# Chronos-Pad.net
KiCad netlist of a schematic drawn in EasyEDA Pro
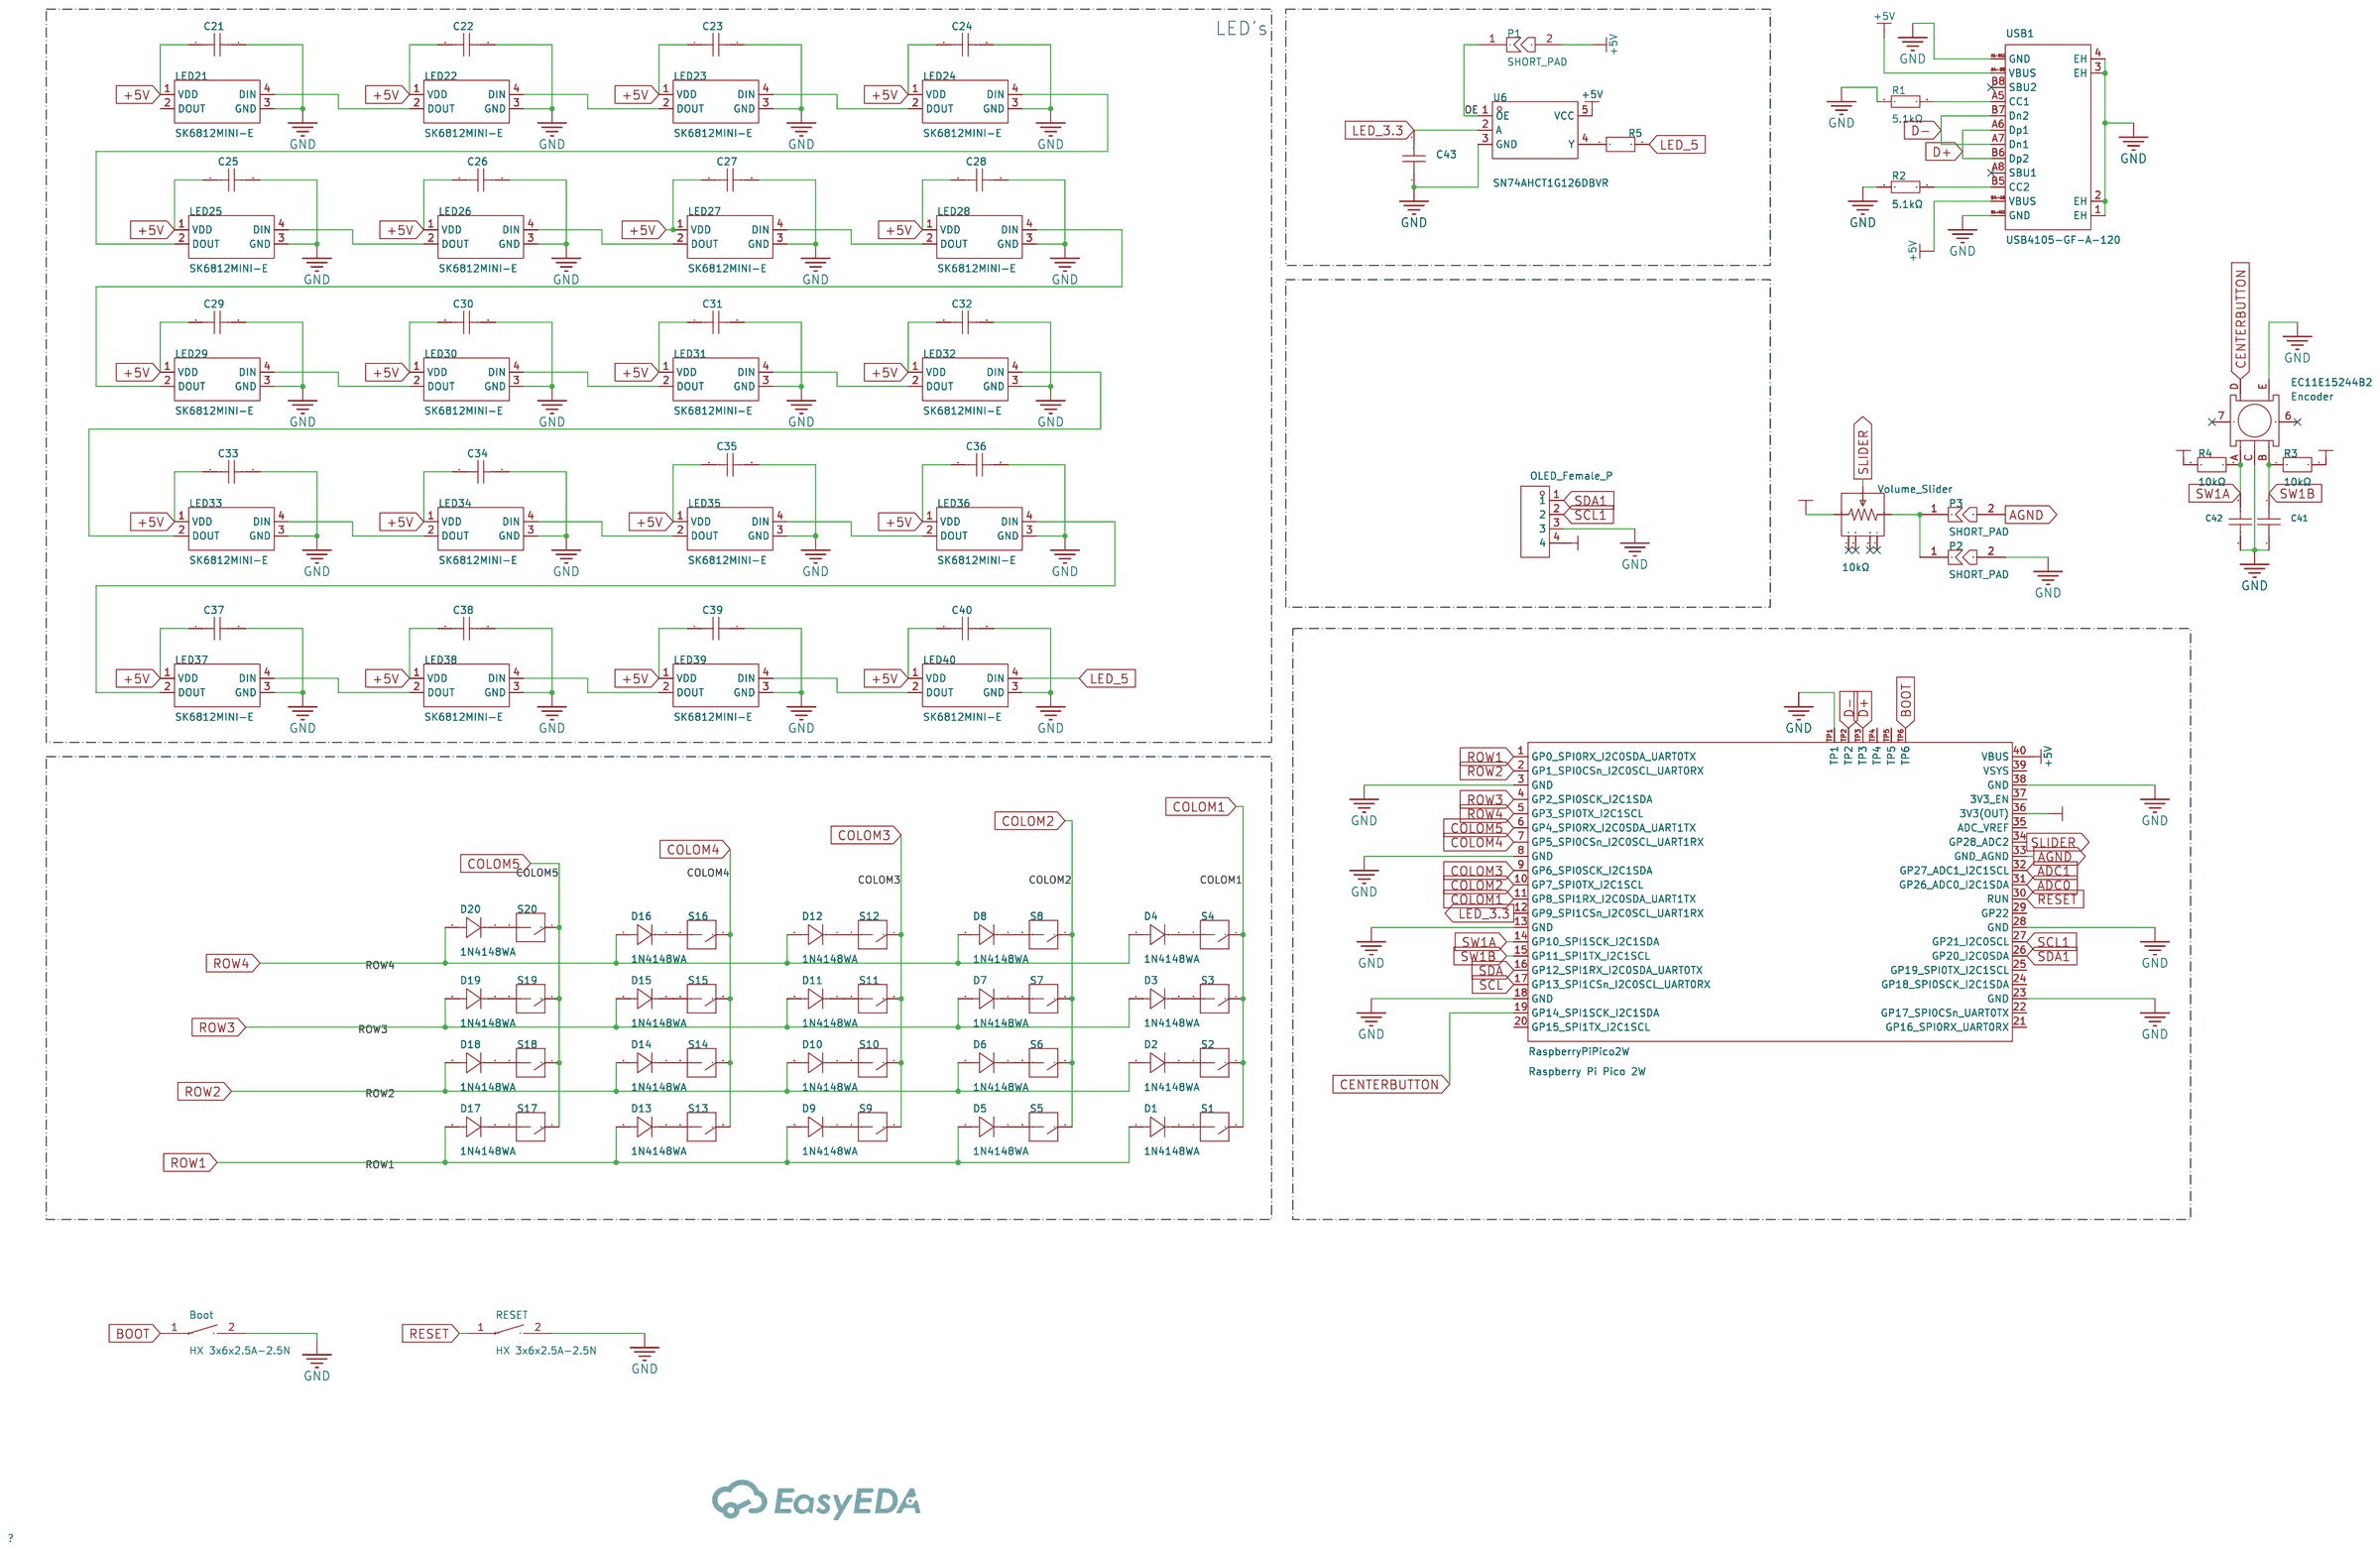
[diagram p0: schematic sheet]

(export (version "E")
  (design (tool "Eeschema 10.0.6"))
  (components
    (comp (ref "Boot")
      (value "HX 3x6x2.5A-2.5N")
      (footprint "easyedapro:SW-SMD_HX-TS-1101-C-W")
      (fields (field (name "Manufacturer") "hanxia(韩下)"))
      (libsource (lib "easyedapro") (part "HX TS-1101-C-W"))
    )
    (comp (ref "C21")
      (value "100nF")
      (footprint "easyedapro:C0603")
      (description "Capacitance:100nF Tolerance:±10% Tolerance:±10% Voltage Rating:50V Temperature Coefficient:X7R")
      (fields
        (field (name "Manufacturer Part") "CC0805KRX7R9BB104")
        (field (name "Manufacturer") "YAGEO(国巨)")
      )
      (libsource (lib "easyedapro") (part "NL0603B104M500CPBN"))
    )
    (comp (ref "C22")
      (value "100nF")
      (footprint "easyedapro:C0603")
      (description "Capacitance:100nF Tolerance:±10% Tolerance:±10% Voltage Rating:50V Temperature Coefficient:X7R")
      (fields
        (field (name "Manufacturer Part") "CC0805KRX7R9BB104")
        (field (name "Manufacturer") "YAGEO(国巨)")
      )
      (libsource (lib "easyedapro") (part "NL0603B104M500CPBN"))
    )
    (comp (ref "C23")
      (value "100nF")
      (footprint "easyedapro:C0603")
      (description "Capacitance:100nF Tolerance:±10% Tolerance:±10% Voltage Rating:50V Temperature Coefficient:X7R")
      (fields
        (field (name "Manufacturer Part") "CC0805KRX7R9BB104")
        (field (name "Manufacturer") "YAGEO(国巨)")
      )
      (libsource (lib "easyedapro") (part "NL0603B104M500CPBN"))
    )
    (comp (ref "C24")
      (value "100nF")
      (footprint "easyedapro:C0603")
      (description "Capacitance:100nF Tolerance:±10% Tolerance:±10% Voltage Rating:50V Temperature Coefficient:X7R")
      (fields
        (field (name "Manufacturer Part") "CC0805KRX7R9BB104")
        (field (name "Manufacturer") "YAGEO(国巨)")
      )
      (libsource (lib "easyedapro") (part "NL0603B104M500CPBN"))
    )
    (comp (ref "C25")
      (value "100nF")
      (footprint "easyedapro:C0603")
      (description "Capacitance:100nF Tolerance:±10% Tolerance:±10% Voltage Rating:50V Temperature Coefficient:X7R")
      (fields
        (field (name "Manufacturer Part") "CC0805KRX7R9BB104")
        (field (name "Manufacturer") "YAGEO(国巨)")
      )
      (libsource (lib "easyedapro") (part "NL0603B104M500CPBN"))
    )
    (comp (ref "C26")
      (value "100nF")
      (footprint "easyedapro:C0603")
      (description "Capacitance:100nF Tolerance:±10% Tolerance:±10% Voltage Rating:50V Temperature Coefficient:X7R")
      (fields
        (field (name "Manufacturer Part") "CC0805KRX7R9BB104")
        (field (name "Manufacturer") "YAGEO(国巨)")
      )
      (libsource (lib "easyedapro") (part "NL0603B104M500CPBN"))
    )
    (comp (ref "C27")
      (value "100nF")
      (footprint "easyedapro:C0603")
      (description "Capacitance:100nF Tolerance:±10% Tolerance:±10% Voltage Rating:50V Temperature Coefficient:X7R")
      (fields
        (field (name "Manufacturer Part") "CC0805KRX7R9BB104")
        (field (name "Manufacturer") "YAGEO(国巨)")
      )
      (libsource (lib "easyedapro") (part "NL0603B104M500CPBN"))
    )
    (comp (ref "C28")
      (value "100nF")
      (footprint "easyedapro:C0603")
      (description "Capacitance:100nF Tolerance:±10% Tolerance:±10% Voltage Rating:50V Temperature Coefficient:X7R")
      (fields
        (field (name "Manufacturer Part") "CC0805KRX7R9BB104")
        (field (name "Manufacturer") "YAGEO(国巨)")
      )
      (libsource (lib "easyedapro") (part "NL0603B104M500CPBN"))
    )
    (comp (ref "C29")
      (value "100nF")
      (footprint "easyedapro:C0603")
      (description "Capacitance:100nF Tolerance:±10% Tolerance:±10% Voltage Rating:50V Temperature Coefficient:X7R")
      (fields
        (field (name "Manufacturer Part") "CC0805KRX7R9BB104")
        (field (name "Manufacturer") "YAGEO(国巨)")
      )
      (libsource (lib "easyedapro") (part "NL0603B104M500CPBN"))
    )
    (comp (ref "C30")
      (value "100nF")
      (footprint "easyedapro:C0603")
      (description "Capacitance:100nF Tolerance:±10% Tolerance:±10% Voltage Rating:50V Temperature Coefficient:X7R")
      (fields
        (field (name "Manufacturer Part") "CC0805KRX7R9BB104")
        (field (name "Manufacturer") "YAGEO(国巨)")
      )
      (libsource (lib "easyedapro") (part "NL0603B104M500CPBN"))
    )
    (comp (ref "C31")
      (value "100nF")
      (footprint "easyedapro:C0603")
      (description "Capacitance:100nF Tolerance:±10% Tolerance:±10% Voltage Rating:50V Temperature Coefficient:X7R")
      (fields
        (field (name "Manufacturer Part") "CC0805KRX7R9BB104")
        (field (name "Manufacturer") "YAGEO(国巨)")
      )
      (libsource (lib "easyedapro") (part "NL0603B104M500CPBN"))
    )
    (comp (ref "C32")
      (value "100nF")
      (footprint "easyedapro:C0603")
      (description "Capacitance:100nF Tolerance:±10% Tolerance:±10% Voltage Rating:50V Temperature Coefficient:X7R")
      (fields
        (field (name "Manufacturer Part") "CC0805KRX7R9BB104")
        (field (name "Manufacturer") "YAGEO(国巨)")
      )
      (libsource (lib "easyedapro") (part "NL0603B104M500CPBN"))
    )
    (comp (ref "C33")
      (value "100nF")
      (footprint "easyedapro:C0603")
      (description "Capacitance:100nF Tolerance:±10% Tolerance:±10% Voltage Rating:50V Temperature Coefficient:X7R")
      (fields
        (field (name "Manufacturer Part") "CC0805KRX7R9BB104")
        (field (name "Manufacturer") "YAGEO(国巨)")
      )
      (libsource (lib "easyedapro") (part "NL0603B104M500CPBN"))
    )
    (comp (ref "C34")
      (value "100nF")
      (footprint "easyedapro:C0603")
      (description "Capacitance:100nF Tolerance:±10% Tolerance:±10% Voltage Rating:50V Temperature Coefficient:X7R")
      (fields
        (field (name "Manufacturer Part") "CC0805KRX7R9BB104")
        (field (name "Manufacturer") "YAGEO(国巨)")
      )
      (libsource (lib "easyedapro") (part "NL0603B104M500CPBN"))
    )
    (comp (ref "C35")
      (value "100nF")
      (footprint "easyedapro:C0603")
      (description "Capacitance:100nF Tolerance:±10% Tolerance:±10% Voltage Rating:50V Temperature Coefficient:X7R")
      (fields
        (field (name "Manufacturer Part") "CC0805KRX7R9BB104")
        (field (name "Manufacturer") "YAGEO(国巨)")
      )
      (libsource (lib "easyedapro") (part "NL0603B104M500CPBN"))
    )
    (comp (ref "C36")
      (value "100nF")
      (footprint "easyedapro:C0603")
      (description "Capacitance:100nF Tolerance:±10% Tolerance:±10% Voltage Rating:50V Temperature Coefficient:X7R")
      (fields
        (field (name "Manufacturer Part") "CC0805KRX7R9BB104")
        (field (name "Manufacturer") "YAGEO(国巨)")
      )
      (libsource (lib "easyedapro") (part "NL0603B104M500CPBN"))
    )
    (comp (ref "C37")
      (value "100nF")
      (footprint "easyedapro:C0603")
      (description "Capacitance:100nF Tolerance:±10% Tolerance:±10% Voltage Rating:50V Temperature Coefficient:X7R")
      (fields
        (field (name "Manufacturer Part") "CC0805KRX7R9BB104")
        (field (name "Manufacturer") "YAGEO(国巨)")
      )
      (libsource (lib "easyedapro") (part "NL0603B104M500CPBN"))
    )
    (comp (ref "C38")
      (value "100nF")
      (footprint "easyedapro:C0603")
      (description "Capacitance:100nF Tolerance:±10% Tolerance:±10% Voltage Rating:50V Temperature Coefficient:X7R")
      (fields
        (field (name "Manufacturer Part") "CC0805KRX7R9BB104")
        (field (name "Manufacturer") "YAGEO(国巨)")
      )
      (libsource (lib "easyedapro") (part "NL0603B104M500CPBN"))
    )
    (comp (ref "C39")
      (value "100nF")
      (footprint "easyedapro:C0603")
      (description "Capacitance:100nF Tolerance:±10% Tolerance:±10% Voltage Rating:50V Temperature Coefficient:X7R")
      (fields
        (field (name "Manufacturer Part") "CC0805KRX7R9BB104")
        (field (name "Manufacturer") "YAGEO(国巨)")
      )
      (libsource (lib "easyedapro") (part "NL0603B104M500CPBN"))
    )
    (comp (ref "C40")
      (value "100nF")
      (footprint "easyedapro:C0603")
      (description "Capacitance:100nF Tolerance:±10% Tolerance:±10% Voltage Rating:50V Temperature Coefficient:X7R")
      (fields
        (field (name "Manufacturer Part") "CC0805KRX7R9BB104")
        (field (name "Manufacturer") "YAGEO(国巨)")
      )
      (libsource (lib "easyedapro") (part "NL0603B104M500CPBN"))
    )
    (comp (ref "C41")
      (value "100nF")
      (footprint "easyedapro:C0805")
      (description "Capacitance:100nF Tolerance:±10% Tolerance:±10% Voltage Rating:50V Temperature Coefficient:X7R")
      (fields
        (field (name "Manufacturer Part") "CC0805KRX7R9BB104")
        (field (name "Manufacturer") "YAGEO(国巨)")
      )
      (libsource (lib "easyedapro") (part "CC0805JRX7R9BB103"))
    )
    (comp (ref "C42")
      (value "100nF")
      (footprint "easyedapro:C0805")
      (description "Capacitance:100nF Tolerance:±10% Tolerance:±10% Voltage Rating:50V Temperature Coefficient:X7R")
      (fields
        (field (name "Manufacturer Part") "CC0805KRX7R9BB104")
        (field (name "Manufacturer") "YAGEO(国巨)")
      )
      (libsource (lib "easyedapro") (part "CC0805JRX7R9BB103"))
    )
    (comp (ref "C43")
      (value "100nF")
      (footprint "easyedapro:C0603")
      (description "Capacitance:100nF Tolerance:±10% Tolerance:±10% Voltage Rating:50V Temperature Coefficient:X7R")
      (fields
        (field (name "Manufacturer Part") "CC0805KRX7R9BB104")
        (field (name "Manufacturer") "YAGEO(国巨)")
      )
      (libsource (lib "easyedapro") (part "NL0603B104M500CPBN"))
    )
    (comp (ref "D1")
      (value "1N4148WA")
      (footprint "easyedapro:SOD-323_L1.7-W1.3-LS2.7-RD")
      (fields (field (name "Manufacturer") "PJSEMI(平晶微)"))
      (libsource (lib "easyedapro") (part "1N4148WS_C5381436"))
    )
    (comp (ref "D2")
      (value "1N4148WA")
      (footprint "easyedapro:SOD-323_L1.7-W1.3-LS2.7-RD")
      (fields (field (name "Manufacturer") "PJSEMI(平晶微)"))
      (libsource (lib "easyedapro") (part "1N4148WS_C5381436"))
    )
    (comp (ref "D3")
      (value "1N4148WA")
      (footprint "easyedapro:SOD-323_L1.7-W1.3-LS2.7-RD")
      (fields (field (name "Manufacturer") "PJSEMI(平晶微)"))
      (libsource (lib "easyedapro") (part "1N4148WS_C5381436"))
    )
    (comp (ref "D4")
      (value "1N4148WA")
      (footprint "easyedapro:SOD-323_L1.7-W1.3-LS2.7-RD")
      (fields (field (name "Manufacturer") "PJSEMI(平晶微)"))
      (libsource (lib "easyedapro") (part "1N4148WS_C5381436"))
    )
    (comp (ref "D5")
      (value "1N4148WA")
      (footprint "easyedapro:SOD-323_L1.7-W1.3-LS2.7-RD")
      (fields (field (name "Manufacturer") "PJSEMI(平晶微)"))
      (libsource (lib "easyedapro") (part "1N4148WS_C5381436"))
    )
    (comp (ref "D6")
      (value "1N4148WA")
      (footprint "easyedapro:SOD-323_L1.7-W1.3-LS2.7-RD")
      (fields (field (name "Manufacturer") "PJSEMI(平晶微)"))
      (libsource (lib "easyedapro") (part "1N4148WS_C5381436"))
    )
    (comp (ref "D7")
      (value "1N4148WA")
      (footprint "easyedapro:SOD-323_L1.7-W1.3-LS2.7-RD")
      (fields (field (name "Manufacturer") "PJSEMI(平晶微)"))
      (libsource (lib "easyedapro") (part "1N4148WS_C5381436"))
    )
    (comp (ref "D8")
      (value "1N4148WA")
      (footprint "easyedapro:SOD-323_L1.7-W1.3-LS2.7-RD")
      (fields (field (name "Manufacturer") "PJSEMI(平晶微)"))
      (libsource (lib "easyedapro") (part "1N4148WS_C5381436"))
    )
    (comp (ref "D9")
      (value "1N4148WA")
      (footprint "easyedapro:SOD-323_L1.7-W1.3-LS2.7-RD")
      (fields (field (name "Manufacturer") "PJSEMI(平晶微)"))
      (libsource (lib "easyedapro") (part "1N4148WS_C5381436"))
    )
    (comp (ref "D10")
      (value "1N4148WA")
      (footprint "easyedapro:SOD-323_L1.7-W1.3-LS2.7-RD")
      (fields (field (name "Manufacturer") "PJSEMI(平晶微)"))
      (libsource (lib "easyedapro") (part "1N4148WS_C5381436"))
    )
    (comp (ref "D11")
      (value "1N4148WA")
      (footprint "easyedapro:SOD-323_L1.7-W1.3-LS2.7-RD")
      (fields (field (name "Manufacturer") "PJSEMI(平晶微)"))
      (libsource (lib "easyedapro") (part "1N4148WS_C5381436"))
    )
    (comp (ref "D12")
      (value "1N4148WA")
      (footprint "easyedapro:SOD-323_L1.7-W1.3-LS2.7-RD")
      (fields (field (name "Manufacturer") "PJSEMI(平晶微)"))
      (libsource (lib "easyedapro") (part "1N4148WS_C5381436"))
    )
    (comp (ref "D13")
      (value "1N4148WA")
      (footprint "easyedapro:SOD-323_L1.7-W1.3-LS2.7-RD")
      (fields (field (name "Manufacturer") "PJSEMI(平晶微)"))
      (libsource (lib "easyedapro") (part "1N4148WS_C5381436"))
    )
    (comp (ref "D14")
      (value "1N4148WA")
      (footprint "easyedapro:SOD-323_L1.7-W1.3-LS2.7-RD")
      (fields (field (name "Manufacturer") "PJSEMI(平晶微)"))
      (libsource (lib "easyedapro") (part "1N4148WS_C5381436"))
    )
    (comp (ref "D15")
      (value "1N4148WA")
      (footprint "easyedapro:SOD-323_L1.7-W1.3-LS2.7-RD")
      (fields (field (name "Manufacturer") "PJSEMI(平晶微)"))
      (libsource (lib "easyedapro") (part "1N4148WS_C5381436"))
    )
    (comp (ref "D16")
      (value "1N4148WA")
      (footprint "easyedapro:SOD-323_L1.7-W1.3-LS2.7-RD")
      (fields (field (name "Manufacturer") "PJSEMI(平晶微)"))
      (libsource (lib "easyedapro") (part "1N4148WS_C5381436"))
    )
    (comp (ref "D17")
      (value "1N4148WA")
      (footprint "easyedapro:SOD-323_L1.7-W1.3-LS2.7-RD")
      (fields (field (name "Manufacturer") "PJSEMI(平晶微)"))
      (libsource (lib "easyedapro") (part "1N4148WS_C5381436"))
    )
    (comp (ref "D18")
      (value "1N4148WA")
      (footprint "easyedapro:SOD-323_L1.7-W1.3-LS2.7-RD")
      (fields (field (name "Manufacturer") "PJSEMI(平晶微)"))
      (libsource (lib "easyedapro") (part "1N4148WS_C5381436"))
    )
    (comp (ref "D19")
      (value "1N4148WA")
      (footprint "easyedapro:SOD-323_L1.7-W1.3-LS2.7-RD")
      (fields (field (name "Manufacturer") "PJSEMI(平晶微)"))
      (libsource (lib "easyedapro") (part "1N4148WS_C5381436"))
    )
    (comp (ref "D20")
      (value "1N4148WA")
      (footprint "easyedapro:SOD-323_L1.7-W1.3-LS2.7-RD")
      (fields (field (name "Manufacturer") "PJSEMI(平晶微)"))
      (libsource (lib "easyedapro") (part "1N4148WS_C5381436"))
    )
    (comp (ref "Encoder")
      (value "EC11E15244B2")
      (footprint "easyedapro:SW-TH_EC11XXXXXXXX")
      (fields (field (name "Manufacturer") "ALPSALPINE(阿尔卑斯阿尔派)"))
      (libsource (lib "easyedapro") (part "EC11E15204A3"))
    )
    (comp (ref "LED21")
      (value "SK6812MINI-E")
      (footprint "easyedapro:LED-SMD_L3.2-W2.8-LS5.9_SK6812MINI-E")
      (fields (field (name "Manufacturer") "欧思科光电"))
      (libsource (lib "easyedapro") (part "SK6812MINI-E_C5149201"))
    )
    (comp (ref "LED22")
      (value "SK6812MINI-E")
      (footprint "easyedapro:LED-SMD_L3.2-W2.8-LS5.9_SK6812MINI-E")
      (fields (field (name "Manufacturer") "欧思科光电"))
      (libsource (lib "easyedapro") (part "SK6812MINI-E_C5149201"))
    )
    (comp (ref "LED23")
      (value "SK6812MINI-E")
      (footprint "easyedapro:LED-SMD_L3.2-W2.8-LS5.9_SK6812MINI-E")
      (fields (field (name "Manufacturer") "欧思科光电"))
      (libsource (lib "easyedapro") (part "SK6812MINI-E_C5149201"))
    )
    (comp (ref "LED24")
      (value "SK6812MINI-E")
      (footprint "easyedapro:LED-SMD_L3.2-W2.8-LS5.9_SK6812MINI-E")
      (fields (field (name "Manufacturer") "欧思科光电"))
      (libsource (lib "easyedapro") (part "SK6812MINI-E_C5149201"))
    )
    (comp (ref "LED25")
      (value "SK6812MINI-E")
      (footprint "easyedapro:LED-SMD_L3.2-W2.8-LS5.9_SK6812MINI-E")
      (fields (field (name "Manufacturer") "欧思科光电"))
      (libsource (lib "easyedapro") (part "SK6812MINI-E_C5149201"))
    )
    (comp (ref "LED26")
      (value "SK6812MINI-E")
      (footprint "easyedapro:LED-SMD_L3.2-W2.8-LS5.9_SK6812MINI-E")
      (fields (field (name "Manufacturer") "欧思科光电"))
      (libsource (lib "easyedapro") (part "SK6812MINI-E_C5149201"))
    )
    (comp (ref "LED27")
      (value "SK6812MINI-E")
      (footprint "easyedapro:LED-SMD_L3.2-W2.8-LS5.9_SK6812MINI-E")
      (fields (field (name "Manufacturer") "欧思科光电"))
      (libsource (lib "easyedapro") (part "SK6812MINI-E_C5149201"))
    )
    (comp (ref "LED28")
      (value "SK6812MINI-E")
      (footprint "easyedapro:LED-SMD_L3.2-W2.8-LS5.9_SK6812MINI-E")
      (fields (field (name "Manufacturer") "欧思科光电"))
      (libsource (lib "easyedapro") (part "SK6812MINI-E_C5149201"))
    )
    (comp (ref "LED29")
      (value "SK6812MINI-E")
      (footprint "easyedapro:LED-SMD_L3.2-W2.8-LS5.9_SK6812MINI-E")
      (fields (field (name "Manufacturer") "欧思科光电"))
      (libsource (lib "easyedapro") (part "SK6812MINI-E_C5149201"))
    )
    (comp (ref "LED30")
      (value "SK6812MINI-E")
      (footprint "easyedapro:LED-SMD_L3.2-W2.8-LS5.9_SK6812MINI-E")
      (fields (field (name "Manufacturer") "欧思科光电"))
      (libsource (lib "easyedapro") (part "SK6812MINI-E_C5149201"))
    )
    (comp (ref "LED31")
      (value "SK6812MINI-E")
      (footprint "easyedapro:LED-SMD_L3.2-W2.8-LS5.9_SK6812MINI-E")
      (fields (field (name "Manufacturer") "欧思科光电"))
      (libsource (lib "easyedapro") (part "SK6812MINI-E_C5149201"))
    )
    (comp (ref "LED32")
      (value "SK6812MINI-E")
      (footprint "easyedapro:LED-SMD_L3.2-W2.8-LS5.9_SK6812MINI-E")
      (fields (field (name "Manufacturer") "欧思科光电"))
      (libsource (lib "easyedapro") (part "SK6812MINI-E_C5149201"))
    )
    (comp (ref "LED33")
      (value "SK6812MINI-E")
      (footprint "easyedapro:LED-SMD_L3.2-W2.8-LS5.9_SK6812MINI-E")
      (fields (field (name "Manufacturer") "欧思科光电"))
      (libsource (lib "easyedapro") (part "SK6812MINI-E_C5149201"))
    )
    (comp (ref "LED34")
      (value "SK6812MINI-E")
      (footprint "easyedapro:LED-SMD_L3.2-W2.8-LS5.9_SK6812MINI-E")
      (fields (field (name "Manufacturer") "欧思科光电"))
      (libsource (lib "easyedapro") (part "SK6812MINI-E_C5149201"))
    )
    (comp (ref "LED35")
      (value "SK6812MINI-E")
      (footprint "easyedapro:LED-SMD_L3.2-W2.8-LS5.9_SK6812MINI-E")
      (fields (field (name "Manufacturer") "欧思科光电"))
      (libsource (lib "easyedapro") (part "SK6812MINI-E_C5149201"))
    )
    (comp (ref "LED36")
      (value "SK6812MINI-E")
      (footprint "easyedapro:LED-SMD_L3.2-W2.8-LS5.9_SK6812MINI-E")
      (fields (field (name "Manufacturer") "欧思科光电"))
      (libsource (lib "easyedapro") (part "SK6812MINI-E_C5149201"))
    )
    (comp (ref "LED37")
      (value "SK6812MINI-E")
      (footprint "easyedapro:LED-SMD_L3.2-W2.8-LS5.9_SK6812MINI-E")
      (fields (field (name "Manufacturer") "欧思科光电"))
      (libsource (lib "easyedapro") (part "SK6812MINI-E_C5149201"))
    )
    (comp (ref "LED38")
      (value "SK6812MINI-E")
      (footprint "easyedapro:LED-SMD_L3.2-W2.8-LS5.9_SK6812MINI-E")
      (fields (field (name "Manufacturer") "欧思科光电"))
      (libsource (lib "easyedapro") (part "SK6812MINI-E_C5149201"))
    )
    (comp (ref "LED39")
      (value "SK6812MINI-E")
      (footprint "easyedapro:LED-SMD_L3.2-W2.8-LS5.9_SK6812MINI-E")
      (fields (field (name "Manufacturer") "欧思科光电"))
      (libsource (lib "easyedapro") (part "SK6812MINI-E_C5149201"))
    )
    (comp (ref "LED40")
      (value "SK6812MINI-E")
      (footprint "easyedapro:LED-SMD_L3.2-W2.8-LS5.9_SK6812MINI-E")
      (fields (field (name "Manufacturer") "欧思科光电"))
      (libsource (lib "easyedapro") (part "SK6812MINI-E_C5149201"))
    )
    (comp (ref "OLED_Female_P")
      (value "~")
      (footprint "easyedapro:CONN-TH_4P-P2.50-XH2.54-4P")
      (fields (field (name "Manufacturer Part") "XH-2.54-4P"))
      (libsource (lib "easyedapro") (part "XH-2.54-4P"))
    )
    (comp (ref "P1")
      (value "SHORT_PAD")
      (footprint "easyedapro:SHORT_PAD")
      (libsource (lib "easyedapro") (part "SHORT_PAD"))
    )
    (comp (ref "P2")
      (value "SHORT_PAD")
      (footprint "easyedapro:SHORT_PAD")
      (libsource (lib "easyedapro") (part "SHORT_PAD"))
    )
    (comp (ref "P3")
      (value "SHORT_PAD")
      (footprint "easyedapro:SHORT_PAD")
      (libsource (lib "easyedapro") (part "SHORT_PAD"))
    )
    (comp (ref "R1")
      (value "5.1kΩ")
      (footprint "easyedapro:R0805")
      (fields (field (name "Manufacturer Part") "MCR10EZPF5101") (field (name "Manufacturer") "ROHM(罗姆)"))
      (libsource (lib "easyedapro") (part "MCR10EZPF5101"))
    )
    (comp (ref "R2")
      (value "5.1kΩ")
      (footprint "easyedapro:R0805")
      (fields (field (name "Manufacturer Part") "MCR10EZPF5101") (field (name "Manufacturer") "ROHM(罗姆)"))
      (libsource (lib "easyedapro") (part "MCR10EZPF5101"))
    )
    (comp (ref "R3")
      (value "10kΩ")
      (footprint "easyedapro:R0805")
      (fields (field (name "Manufacturer Part") "SCR0805J10K") (field (name "Manufacturer") "VO(翔胜)"))
      (libsource (lib "easyedapro") (part "SCR0805J10K"))
    )
    (comp (ref "R4")
      (value "10kΩ")
      (footprint "easyedapro:R0805")
      (fields (field (name "Manufacturer Part") "SCR0805J10K") (field (name "Manufacturer") "VO(翔胜)"))
      (libsource (lib "easyedapro") (part "SCR0805J10K"))
    )
    (comp (ref "R5")
      (value "300Ω")
      (footprint "easyedapro:R0805")
      (fields
        (field (name "Manufacturer Part") "CRCW0805300RFKEA")
        (field (name "Manufacturer") "VISHAY(威世)")
      )
      (libsource (lib "easyedapro") (part "CRCW0805300RFKEA"))
    )
    (comp (ref "RaspberryPiPico2W")
      (value "Raspberry Pi Pico 2W")
      (footprint "easyedapro:COMM-SMD_L51.0-W21.0-P2.54_PICOW")
      (fields (field (name "Manufacturer") "Raspberry Pi(树莓派)"))
      (libsource (lib "easyedapro") (part "RASPBERRY PI PICO 2W"))
    )
    (comp (ref "RESET")
      (value "HX 3x6x2.5A-2.5N")
      (footprint "easyedapro:SW-SMD_HX-TS-1101-C-W")
      (fields (field (name "Manufacturer") "hanxia(韩下)"))
      (libsource (lib "easyedapro") (part "HX TS-1101-C-W"))
    )
    (comp (ref "S1")
      (value "adafruit_electromech_KBD_SWITCH_KAILH_SOCKET_BOX_JADE_KAILH_SOCKET")
      (footprint "easyedapro:KAILH_SOCKET")
      (libsource (lib "easyedapro") (part "adafruit_electromech_KBD_SWITCH_KAILH_SOCKET_BOX_JADE_KAILH_SOCKET"))
    )
    (comp (ref "S2")
      (value "adafruit_electromech_KBD_SWITCH_KAILH_SOCKET_BOX_JADE_KAILH_SOCKET")
      (footprint "easyedapro:KAILH_SOCKET")
      (libsource (lib "easyedapro") (part "adafruit_electromech_KBD_SWITCH_KAILH_SOCKET_BOX_JADE_KAILH_SOCKET"))
    )
    (comp (ref "S3")
      (value "adafruit_electromech_KBD_SWITCH_KAILH_SOCKET_BOX_JADE_KAILH_SOCKET")
      (footprint "easyedapro:KAILH_SOCKET")
      (libsource (lib "easyedapro") (part "adafruit_electromech_KBD_SWITCH_KAILH_SOCKET_BOX_JADE_KAILH_SOCKET"))
    )
    (comp (ref "S4")
      (value "adafruit_electromech_KBD_SWITCH_KAILH_SOCKET_BOX_JADE_KAILH_SOCKET")
      (footprint "easyedapro:KAILH_SOCKET")
      (libsource (lib "easyedapro") (part "adafruit_electromech_KBD_SWITCH_KAILH_SOCKET_BOX_JADE_KAILH_SOCKET"))
    )
    (comp (ref "S5")
      (value "adafruit_electromech_KBD_SWITCH_KAILH_SOCKET_BOX_JADE_KAILH_SOCKET")
      (footprint "easyedapro:KAILH_SOCKET")
      (libsource (lib "easyedapro") (part "adafruit_electromech_KBD_SWITCH_KAILH_SOCKET_BOX_JADE_KAILH_SOCKET"))
    )
    (comp (ref "S6")
      (value "adafruit_electromech_KBD_SWITCH_KAILH_SOCKET_BOX_JADE_KAILH_SOCKET")
      (footprint "easyedapro:KAILH_SOCKET")
      (libsource (lib "easyedapro") (part "adafruit_electromech_KBD_SWITCH_KAILH_SOCKET_BOX_JADE_KAILH_SOCKET"))
    )
    (comp (ref "S7")
      (value "adafruit_electromech_KBD_SWITCH_KAILH_SOCKET_BOX_JADE_KAILH_SOCKET")
      (footprint "easyedapro:KAILH_SOCKET")
      (libsource (lib "easyedapro") (part "adafruit_electromech_KBD_SWITCH_KAILH_SOCKET_BOX_JADE_KAILH_SOCKET"))
    )
    (comp (ref "S8")
      (value "adafruit_electromech_KBD_SWITCH_KAILH_SOCKET_BOX_JADE_KAILH_SOCKET")
      (footprint "easyedapro:KAILH_SOCKET")
      (libsource (lib "easyedapro") (part "adafruit_electromech_KBD_SWITCH_KAILH_SOCKET_BOX_JADE_KAILH_SOCKET"))
    )
    (comp (ref "S9")
      (value "adafruit_electromech_KBD_SWITCH_KAILH_SOCKET_BOX_JADE_KAILH_SOCKET")
      (footprint "easyedapro:KAILH_SOCKET")
      (libsource (lib "easyedapro") (part "adafruit_electromech_KBD_SWITCH_KAILH_SOCKET_BOX_JADE_KAILH_SOCKET"))
    )
    (comp (ref "S10")
      (value "adafruit_electromech_KBD_SWITCH_KAILH_SOCKET_BOX_JADE_KAILH_SOCKET")
      (footprint "easyedapro:KAILH_SOCKET")
      (libsource (lib "easyedapro") (part "adafruit_electromech_KBD_SWITCH_KAILH_SOCKET_BOX_JADE_KAILH_SOCKET"))
    )
    (comp (ref "S11")
      (value "adafruit_electromech_KBD_SWITCH_KAILH_SOCKET_BOX_JADE_KAILH_SOCKET")
      (footprint "easyedapro:KAILH_SOCKET")
      (libsource (lib "easyedapro") (part "adafruit_electromech_KBD_SWITCH_KAILH_SOCKET_BOX_JADE_KAILH_SOCKET"))
    )
    (comp (ref "S12")
      (value "adafruit_electromech_KBD_SWITCH_KAILH_SOCKET_BOX_JADE_KAILH_SOCKET")
      (footprint "easyedapro:KAILH_SOCKET")
      (libsource (lib "easyedapro") (part "adafruit_electromech_KBD_SWITCH_KAILH_SOCKET_BOX_JADE_KAILH_SOCKET"))
    )
    (comp (ref "S13")
      (value "adafruit_electromech_KBD_SWITCH_KAILH_SOCKET_BOX_JADE_KAILH_SOCKET")
      (footprint "easyedapro:KAILH_SOCKET")
      (libsource (lib "easyedapro") (part "adafruit_electromech_KBD_SWITCH_KAILH_SOCKET_BOX_JADE_KAILH_SOCKET"))
    )
    (comp (ref "S14")
      (value "adafruit_electromech_KBD_SWITCH_KAILH_SOCKET_BOX_JADE_KAILH_SOCKET")
      (footprint "easyedapro:KAILH_SOCKET")
      (libsource (lib "easyedapro") (part "adafruit_electromech_KBD_SWITCH_KAILH_SOCKET_BOX_JADE_KAILH_SOCKET"))
    )
    (comp (ref "S15")
      (value "adafruit_electromech_KBD_SWITCH_KAILH_SOCKET_BOX_JADE_KAILH_SOCKET")
      (footprint "easyedapro:KAILH_SOCKET")
      (libsource (lib "easyedapro") (part "adafruit_electromech_KBD_SWITCH_KAILH_SOCKET_BOX_JADE_KAILH_SOCKET"))
    )
    (comp (ref "S16")
      (value "adafruit_electromech_KBD_SWITCH_KAILH_SOCKET_BOX_JADE_KAILH_SOCKET")
      (footprint "easyedapro:KAILH_SOCKET")
      (libsource (lib "easyedapro") (part "adafruit_electromech_KBD_SWITCH_KAILH_SOCKET_BOX_JADE_KAILH_SOCKET"))
    )
    (comp (ref "S17")
      (value "adafruit_electromech_KBD_SWITCH_KAILH_SOCKET_BOX_JADE_KAILH_SOCKET")
      (footprint "easyedapro:KAILH_SOCKET")
      (libsource (lib "easyedapro") (part "adafruit_electromech_KBD_SWITCH_KAILH_SOCKET_BOX_JADE_KAILH_SOCKET"))
    )
    (comp (ref "S18")
      (value "adafruit_electromech_KBD_SWITCH_KAILH_SOCKET_BOX_JADE_KAILH_SOCKET")
      (footprint "easyedapro:KAILH_SOCKET")
      (libsource (lib "easyedapro") (part "adafruit_electromech_KBD_SWITCH_KAILH_SOCKET_BOX_JADE_KAILH_SOCKET"))
    )
    (comp (ref "S19")
      (value "adafruit_electromech_KBD_SWITCH_KAILH_SOCKET_BOX_JADE_KAILH_SOCKET")
      (footprint "easyedapro:KAILH_SOCKET")
      (libsource (lib "easyedapro") (part "adafruit_electromech_KBD_SWITCH_KAILH_SOCKET_BOX_JADE_KAILH_SOCKET"))
    )
    (comp (ref "S20")
      (value "adafruit_electromech_KBD_SWITCH_KAILH_SOCKET_BOX_JADE_KAILH_SOCKET")
      (footprint "easyedapro:KAILH_SOCKET")
      (libsource (lib "easyedapro") (part "adafruit_electromech_KBD_SWITCH_KAILH_SOCKET_BOX_JADE_KAILH_SOCKET"))
    )
    (comp (ref "U6")
      (value "SN74AHCT1G126DBVR")
      (footprint "easyedapro:SOT-23-5_L3.0-W1.7-P0.95-LS2.8-BR")
      (fields (field (name "Manufacturer") "TI(德州仪器)"))
      (libsource (lib "easyedapro") (part "SN74AHCT1G126DBVR"))
    )
    (comp (ref "USB1")
      (value "USB4105-GF-A-120")
      (footprint "easyedapro:USB-C-SMD_MC-311D")
      (fields (field (name "Manufacturer") "GCT"))
      (libsource (lib "easyedapro") (part "USB4105-GF-A-120"))
    )
    (comp (ref "Volume_Slider")
      (value "10kΩ")
      (footprint "easyedapro:RES-ADJ-TH_PTA6043-2015DPB103")
      (description "Resistance:10kΩ Tolerance:±20% Tolerance:±20% Power(Watts):250mW")
      (fields (field (name "Manufacturer Part") "PTA6043-2015DPB103") (field (name "Manufacturer") "BOURNS"))
      (libsource (lib "easyedapro") (part "PTA6043-2015DPB103"))
    )
  )
  (nets
    (net (code "1") (name "+3.3V") (class "Default")
      (node (ref "OLED_Female_P") (pin "4") (pinfunction "4_4") (pintype "input"))
      (node (ref "R3") (pin "2") (pinfunction "2_2") (pintype "unspecified"))
      (node (ref "R4") (pin "1") (pinfunction "1_1") (pintype "unspecified"))
      (node (ref "RaspberryPiPico2W") (pin "36") (pinfunction "3V3(OUT)_36") (pintype "unspecified"))
      (node (ref "Volume_Slider") (pin "3") (pinfunction "3_3") (pintype "unspecified"))
    )
    (net (code "2") (name "+5V") (class "Default")
      (node (ref "C21") (pin "1") (pinfunction "1_1") (pintype "unspecified"))
      (node (ref "C22") (pin "1") (pinfunction "1_1") (pintype "unspecified"))
      (node (ref "C23") (pin "1") (pinfunction "1_1") (pintype "unspecified"))
      (node (ref "C24") (pin "1") (pinfunction "1_1") (pintype "unspecified"))
      (node (ref "C25") (pin "1") (pinfunction "1_1") (pintype "unspecified"))
      (node (ref "C26") (pin "1") (pinfunction "1_1") (pintype "unspecified"))
      (node (ref "C27") (pin "1") (pinfunction "1_1") (pintype "unspecified"))
      (node (ref "C28") (pin "1") (pinfunction "1_1") (pintype "unspecified"))
      (node (ref "C29") (pin "1") (pinfunction "1_1") (pintype "unspecified"))
      (node (ref "C30") (pin "1") (pinfunction "1_1") (pintype "unspecified"))
      (node (ref "C31") (pin "1") (pinfunction "1_1") (pintype "unspecified"))
      (node (ref "C32") (pin "1") (pinfunction "1_1") (pintype "unspecified"))
      (node (ref "C33") (pin "1") (pinfunction "1_1") (pintype "unspecified"))
      (node (ref "C34") (pin "1") (pinfunction "1_1") (pintype "unspecified"))
      (node (ref "C35") (pin "1") (pinfunction "1_1") (pintype "unspecified"))
      (node (ref "C36") (pin "1") (pinfunction "1_1") (pintype "unspecified"))
      (node (ref "C37") (pin "1") (pinfunction "1_1") (pintype "unspecified"))
      (node (ref "C38") (pin "1") (pinfunction "1_1") (pintype "unspecified"))
      (node (ref "C39") (pin "1") (pinfunction "1_1") (pintype "unspecified"))
      (node (ref "C40") (pin "1") (pinfunction "1_1") (pintype "unspecified"))
      (node (ref "LED21") (pin "1") (pinfunction "VDD_1") (pintype "unspecified"))
      (node (ref "LED22") (pin "1") (pinfunction "VDD_1") (pintype "unspecified"))
      (node (ref "LED23") (pin "1") (pinfunction "VDD_1") (pintype "unspecified"))
      (node (ref "LED24") (pin "1") (pinfunction "VDD_1") (pintype "unspecified"))
      (node (ref "LED25") (pin "1") (pinfunction "VDD_1") (pintype "unspecified"))
      (node (ref "LED26") (pin "1") (pinfunction "VDD_1") (pintype "unspecified"))
      (node (ref "LED27") (pin "1") (pinfunction "VDD_1") (pintype "unspecified"))
      (node (ref "LED28") (pin "1") (pinfunction "VDD_1") (pintype "unspecified"))
      (node (ref "LED29") (pin "1") (pinfunction "VDD_1") (pintype "unspecified"))
      (node (ref "LED30") (pin "1") (pinfunction "VDD_1") (pintype "unspecified"))
      (node (ref "LED31") (pin "1") (pinfunction "VDD_1") (pintype "unspecified"))
      (node (ref "LED32") (pin "1") (pinfunction "VDD_1") (pintype "unspecified"))
      (node (ref "LED33") (pin "1") (pinfunction "VDD_1") (pintype "unspecified"))
      (node (ref "LED34") (pin "1") (pinfunction "VDD_1") (pintype "unspecified"))
      (node (ref "LED35") (pin "1") (pinfunction "VDD_1") (pintype "unspecified"))
      (node (ref "LED36") (pin "1") (pinfunction "VDD_1") (pintype "unspecified"))
      (node (ref "LED37") (pin "1") (pinfunction "VDD_1") (pintype "unspecified"))
      (node (ref "LED38") (pin "1") (pinfunction "VDD_1") (pintype "unspecified"))
      (node (ref "LED39") (pin "1") (pinfunction "VDD_1") (pintype "unspecified"))
      (node (ref "LED40") (pin "1") (pinfunction "VDD_1") (pintype "unspecified"))
      (node (ref "P1") (pin "2") (pinfunction "2_2") (pintype "input"))
      (node (ref "RaspberryPiPico2W") (pin "40") (pinfunction "VBUS_40") (pintype "unspecified"))
      (node (ref "U6") (pin "5") (pinfunction "VCC_5") (pintype "input"))
      (node (ref "USB1") (pin "A4-B9") (pinfunction "VBUS_A4-B9") (pintype "unspecified"))
      (node (ref "USB1") (pin "B4-A9") (pinfunction "VBUS_B4-A9") (pintype "unspecified"))
    )
    (net (code "3") (name "/OE") (class "Default")
      (node (ref "P1") (pin "1") (pinfunction "1_1") (pintype "input"))
      (node (ref "U6") (pin "1") (pinfunction "OE_1") (pintype "input"))
    )
    (net (code "4") (name "ADC0") (class "Default")
      (node (ref "RaspberryPiPico2W") (pin "31") (pinfunction "GP26_ADC0_I2C1SDA_31") (pintype "unspecified"))
    )
    (net (code "5") (name "ADC1") (class "Default")
      (node (ref "RaspberryPiPico2W") (pin "32") (pinfunction "GP27_ADC1_I2C1SCL_32") (pintype "unspecified"))
    )
    (net (code "6") (name "AGND") (class "Default")
      (node (ref "P3") (pin "2") (pinfunction "2_2") (pintype "input"))
      (node (ref "RaspberryPiPico2W") (pin "33") (pinfunction "GND_AGND_33") (pintype "unspecified"))
    )
    (net (code "7") (name "BOOT") (class "Default")
      (node (ref "Boot") (pin "1") (pinfunction "1_1") (pintype "unspecified"))
      (node (ref "RaspberryPiPico2W") (pin "TP6") (pinfunction "TP6_TP6") (pintype "unspecified"))
    )
    (net (code "8") (name "CENTERBUTTON") (class "Default")
      (node (ref "Encoder") (pin "D") (pinfunction "D_D") (pintype "unspecified"))
      (node (ref "RaspberryPiPico2W") (pin "19") (pinfunction "GP14_SPI1SCK_I2C1SDA_19") (pintype "unspecified"))
    )
    (net (code "9") (name "COLOM1") (class "Default")
      (node (ref "RaspberryPiPico2W") (pin "11") (pinfunction "GP8_SPI1RX_I2C0SDA_UART1TX_11") (pintype "unspecified"))
      (node (ref "S1") (pin "1") (pinfunction "1_1") (pintype "input"))
      (node (ref "S2") (pin "1") (pinfunction "1_1") (pintype "input"))
      (node (ref "S3") (pin "1") (pinfunction "1_1") (pintype "input"))
      (node (ref "S4") (pin "1") (pinfunction "1_1") (pintype "input"))
    )
    (net (code "10") (name "COLOM2") (class "Default")
      (node (ref "RaspberryPiPico2W") (pin "10") (pinfunction "GP7_SPI0TX_I2C1SCL_10") (pintype "unspecified"))
      (node (ref "S5") (pin "1") (pinfunction "1_1") (pintype "input"))
      (node (ref "S6") (pin "1") (pinfunction "1_1") (pintype "input"))
      (node (ref "S7") (pin "1") (pinfunction "1_1") (pintype "input"))
      (node (ref "S8") (pin "1") (pinfunction "1_1") (pintype "input"))
    )
    (net (code "11") (name "COLOM3") (class "Default")
      (node (ref "RaspberryPiPico2W") (pin "9") (pinfunction "GP6_SPI0SCK_I2C1SDA_9") (pintype "unspecified"))
      (node (ref "S10") (pin "1") (pinfunction "1_1") (pintype "input"))
      (node (ref "S11") (pin "1") (pinfunction "1_1") (pintype "input"))
      (node (ref "S12") (pin "1") (pinfunction "1_1") (pintype "input"))
      (node (ref "S9") (pin "1") (pinfunction "1_1") (pintype "input"))
    )
    (net (code "12") (name "COLOM4") (class "Default")
      (node (ref "RaspberryPiPico2W") (pin "7") (pinfunction "GP5_SPI0CSn_I2C0SCL_UART1RX_7") (pintype "unspecified"))
      (node (ref "S13") (pin "1") (pinfunction "1_1") (pintype "input"))
      (node (ref "S14") (pin "1") (pinfunction "1_1") (pintype "input"))
      (node (ref "S15") (pin "1") (pinfunction "1_1") (pintype "input"))
      (node (ref "S16") (pin "1") (pinfunction "1_1") (pintype "input"))
    )
    (net (code "13") (name "COLOM5") (class "Default")
      (node (ref "RaspberryPiPico2W") (pin "6") (pinfunction "GP4_SPI0RX_I2C0SDA_UART1TX_6") (pintype "unspecified"))
      (node (ref "S17") (pin "1") (pinfunction "1_1") (pintype "input"))
      (node (ref "S18") (pin "1") (pinfunction "1_1") (pintype "input"))
      (node (ref "S19") (pin "1") (pinfunction "1_1") (pintype "input"))
      (node (ref "S20") (pin "1") (pinfunction "1_1") (pintype "input"))
    )
    (net (code "14") (name "D+") (class "Default")
      (node (ref "RaspberryPiPico2W") (pin "TP3") (pinfunction "TP3_TP3") (pintype "unspecified"))
      (node (ref "USB1") (pin "A6") (pinfunction "Dp1_A6") (pintype "unspecified"))
      (node (ref "USB1") (pin "B6") (pinfunction "Dp2_B6") (pintype "unspecified"))
    )
    (net (code "15") (name "D-") (class "Default")
      (node (ref "RaspberryPiPico2W") (pin "TP2") (pinfunction "TP2_TP2") (pintype "unspecified"))
      (node (ref "USB1") (pin "A7") (pinfunction "Dn1_A7") (pintype "unspecified"))
      (node (ref "USB1") (pin "B7") (pinfunction "Dn2_B7") (pintype "unspecified"))
    )
    (net (code "16") (name "GND") (class "Default")
      (node (ref "Boot") (pin "2") (pinfunction "2_2") (pintype "unspecified"))
      (node (ref "C21") (pin "2") (pinfunction "2_2") (pintype "unspecified"))
      (node (ref "C22") (pin "2") (pinfunction "2_2") (pintype "unspecified"))
      (node (ref "C23") (pin "2") (pinfunction "2_2") (pintype "unspecified"))
      (node (ref "C24") (pin "2") (pinfunction "2_2") (pintype "unspecified"))
      (node (ref "C25") (pin "2") (pinfunction "2_2") (pintype "unspecified"))
      (node (ref "C26") (pin "2") (pinfunction "2_2") (pintype "unspecified"))
      (node (ref "C27") (pin "2") (pinfunction "2_2") (pintype "unspecified"))
      (node (ref "C28") (pin "2") (pinfunction "2_2") (pintype "unspecified"))
      (node (ref "C29") (pin "2") (pinfunction "2_2") (pintype "unspecified"))
      (node (ref "C30") (pin "2") (pinfunction "2_2") (pintype "unspecified"))
      (node (ref "C31") (pin "2") (pinfunction "2_2") (pintype "unspecified"))
      (node (ref "C32") (pin "2") (pinfunction "2_2") (pintype "unspecified"))
      (node (ref "C33") (pin "2") (pinfunction "2_2") (pintype "unspecified"))
      (node (ref "C34") (pin "2") (pinfunction "2_2") (pintype "unspecified"))
      (node (ref "C35") (pin "2") (pinfunction "2_2") (pintype "unspecified"))
      (node (ref "C36") (pin "2") (pinfunction "2_2") (pintype "unspecified"))
      (node (ref "C37") (pin "2") (pinfunction "2_2") (pintype "unspecified"))
      (node (ref "C38") (pin "2") (pinfunction "2_2") (pintype "unspecified"))
      (node (ref "C39") (pin "2") (pinfunction "2_2") (pintype "unspecified"))
      (node (ref "C40") (pin "2") (pinfunction "2_2") (pintype "unspecified"))
      (node (ref "C41") (pin "1") (pinfunction "1_1") (pintype "input"))
      (node (ref "C42") (pin "1") (pinfunction "1_1") (pintype "input"))
      (node (ref "C43") (pin "1") (pinfunction "1_1") (pintype "unspecified"))
      (node (ref "Encoder") (pin "C") (pinfunction "C_C") (pintype "unspecified"))
      (node (ref "Encoder") (pin "E") (pinfunction "E_E") (pintype "unspecified"))
      (node (ref "LED21") (pin "3") (pinfunction "GND_3") (pintype "unspecified"))
      (node (ref "LED22") (pin "3") (pinfunction "GND_3") (pintype "unspecified"))
      (node (ref "LED23") (pin "3") (pinfunction "GND_3") (pintype "unspecified"))
      (node (ref "LED24") (pin "3") (pinfunction "GND_3") (pintype "unspecified"))
      (node (ref "LED25") (pin "3") (pinfunction "GND_3") (pintype "unspecified"))
      (node (ref "LED26") (pin "3") (pinfunction "GND_3") (pintype "unspecified"))
      (node (ref "LED27") (pin "3") (pinfunction "GND_3") (pintype "unspecified"))
      (node (ref "LED28") (pin "3") (pinfunction "GND_3") (pintype "unspecified"))
      (node (ref "LED29") (pin "3") (pinfunction "GND_3") (pintype "unspecified"))
      (node (ref "LED30") (pin "3") (pinfunction "GND_3") (pintype "unspecified"))
      (node (ref "LED31") (pin "3") (pinfunction "GND_3") (pintype "unspecified"))
      (node (ref "LED32") (pin "3") (pinfunction "GND_3") (pintype "unspecified"))
      (node (ref "LED33") (pin "3") (pinfunction "GND_3") (pintype "unspecified"))
      (node (ref "LED34") (pin "3") (pinfunction "GND_3") (pintype "unspecified"))
      (node (ref "LED35") (pin "3") (pinfunction "GND_3") (pintype "unspecified"))
      (node (ref "LED36") (pin "3") (pinfunction "GND_3") (pintype "unspecified"))
      (node (ref "LED37") (pin "3") (pinfunction "GND_3") (pintype "unspecified"))
      (node (ref "LED38") (pin "3") (pinfunction "GND_3") (pintype "unspecified"))
      (node (ref "LED39") (pin "3") (pinfunction "GND_3") (pintype "unspecified"))
      (node (ref "LED40") (pin "3") (pinfunction "GND_3") (pintype "unspecified"))
      (node (ref "OLED_Female_P") (pin "3") (pinfunction "3_3") (pintype "input"))
      (node (ref "P2") (pin "2") (pinfunction "2_2") (pintype "input"))
      (node (ref "R1") (pin "1") (pinfunction "1_1") (pintype "unspecified"))
      (node (ref "R2") (pin "1") (pinfunction "1_1") (pintype "unspecified"))
      (node (ref "RESET") (pin "2") (pinfunction "2_2") (pintype "unspecified"))
      (node (ref "RaspberryPiPico2W") (pin "13") (pinfunction "GND_13") (pintype "unspecified"))
      (node (ref "RaspberryPiPico2W") (pin "18") (pinfunction "GND_18") (pintype "unspecified"))
      (node (ref "RaspberryPiPico2W") (pin "23") (pinfunction "GND_23") (pintype "unspecified"))
      (node (ref "RaspberryPiPico2W") (pin "28") (pinfunction "GND_28") (pintype "unspecified"))
      (node (ref "RaspberryPiPico2W") (pin "3") (pinfunction "GND_3") (pintype "unspecified"))
      (node (ref "RaspberryPiPico2W") (pin "38") (pinfunction "GND_38") (pintype "unspecified"))
      (node (ref "RaspberryPiPico2W") (pin "8") (pinfunction "GND_8") (pintype "unspecified"))
      (node (ref "RaspberryPiPico2W") (pin "TP1") (pinfunction "TP1_TP1") (pintype "unspecified"))
      (node (ref "U6") (pin "3") (pinfunction "GND_3") (pintype "input"))
      (node (ref "USB1") (pin "1") (pinfunction "EH_1") (pintype "unspecified"))
      (node (ref "USB1") (pin "2") (pinfunction "EH_2") (pintype "unspecified"))
      (node (ref "USB1") (pin "3") (pinfunction "EH_3") (pintype "unspecified"))
      (node (ref "USB1") (pin "4") (pinfunction "EH_4") (pintype "unspecified"))
      (node (ref "USB1") (pin "A1-B12") (pinfunction "GND_A1-B12") (pintype "unspecified"))
      (node (ref "USB1") (pin "B1-A12") (pinfunction "GND_B1-A12") (pintype "unspecified"))
    )
    (net (code "17") (name "LED_3.3") (class "Default")
      (node (ref "C43") (pin "2") (pinfunction "2_2") (pintype "unspecified"))
      (node (ref "RaspberryPiPico2W") (pin "12") (pinfunction "GP9_SPI1CSn_I2C0SCL_UART1RX_12") (pintype "unspecified"))
      (node (ref "U6") (pin "2") (pinfunction "A_2") (pintype "input"))
    )
    (net (code "18") (name "LED_5") (class "Default")
      (node (ref "LED40") (pin "4") (pinfunction "DIN_4") (pintype "unspecified"))
      (node (ref "R5") (pin "2") (pinfunction "2_2") (pintype "unspecified"))
    )
    (net (code "19") (name "Net-(D1-C)") (class "Default")
      (node (ref "D1") (pin "1") (pinfunction "C_1") (pintype "unspecified"))
      (node (ref "S1") (pin "2") (pinfunction "2_2") (pintype "input"))
    )
    (net (code "20") (name "Net-(D2-C)") (class "Default")
      (node (ref "D2") (pin "1") (pinfunction "C_1") (pintype "unspecified"))
      (node (ref "S2") (pin "2") (pinfunction "2_2") (pintype "input"))
    )
    (net (code "21") (name "Net-(D3-C)") (class "Default")
      (node (ref "D3") (pin "1") (pinfunction "C_1") (pintype "unspecified"))
      (node (ref "S3") (pin "2") (pinfunction "2_2") (pintype "input"))
    )
    (net (code "22") (name "Net-(D4-C)") (class "Default")
      (node (ref "D4") (pin "1") (pinfunction "C_1") (pintype "unspecified"))
      (node (ref "S4") (pin "2") (pinfunction "2_2") (pintype "input"))
    )
    (net (code "23") (name "Net-(D5-C)") (class "Default")
      (node (ref "D5") (pin "1") (pinfunction "C_1") (pintype "unspecified"))
      (node (ref "S5") (pin "2") (pinfunction "2_2") (pintype "input"))
    )
    (net (code "24") (name "Net-(D6-C)") (class "Default")
      (node (ref "D6") (pin "1") (pinfunction "C_1") (pintype "unspecified"))
      (node (ref "S6") (pin "2") (pinfunction "2_2") (pintype "input"))
    )
    (net (code "25") (name "Net-(D7-C)") (class "Default")
      (node (ref "D7") (pin "1") (pinfunction "C_1") (pintype "unspecified"))
      (node (ref "S7") (pin "2") (pinfunction "2_2") (pintype "input"))
    )
    (net (code "26") (name "Net-(D8-C)") (class "Default")
      (node (ref "D8") (pin "1") (pinfunction "C_1") (pintype "unspecified"))
      (node (ref "S8") (pin "2") (pinfunction "2_2") (pintype "input"))
    )
    (net (code "27") (name "Net-(D9-C)") (class "Default")
      (node (ref "D9") (pin "1") (pinfunction "C_1") (pintype "unspecified"))
      (node (ref "S9") (pin "2") (pinfunction "2_2") (pintype "input"))
    )
    (net (code "28") (name "Net-(D10-C)") (class "Default")
      (node (ref "D10") (pin "1") (pinfunction "C_1") (pintype "unspecified"))
      (node (ref "S10") (pin "2") (pinfunction "2_2") (pintype "input"))
    )
    (net (code "29") (name "Net-(D11-C)") (class "Default")
      (node (ref "D11") (pin "1") (pinfunction "C_1") (pintype "unspecified"))
      (node (ref "S11") (pin "2") (pinfunction "2_2") (pintype "input"))
    )
    (net (code "30") (name "Net-(D12-C)") (class "Default")
      (node (ref "D12") (pin "1") (pinfunction "C_1") (pintype "unspecified"))
      (node (ref "S12") (pin "2") (pinfunction "2_2") (pintype "input"))
    )
    (net (code "31") (name "Net-(D13-C)") (class "Default")
      (node (ref "D13") (pin "1") (pinfunction "C_1") (pintype "unspecified"))
      (node (ref "S13") (pin "2") (pinfunction "2_2") (pintype "input"))
    )
    (net (code "32") (name "Net-(D14-C)") (class "Default")
      (node (ref "D14") (pin "1") (pinfunction "C_1") (pintype "unspecified"))
      (node (ref "S14") (pin "2") (pinfunction "2_2") (pintype "input"))
    )
    (net (code "33") (name "Net-(D15-C)") (class "Default")
      (node (ref "D15") (pin "1") (pinfunction "C_1") (pintype "unspecified"))
      (node (ref "S15") (pin "2") (pinfunction "2_2") (pintype "input"))
    )
    (net (code "34") (name "Net-(D16-C)") (class "Default")
      (node (ref "D16") (pin "1") (pinfunction "C_1") (pintype "unspecified"))
      (node (ref "S16") (pin "2") (pinfunction "2_2") (pintype "input"))
    )
    (net (code "35") (name "Net-(D17-C)") (class "Default")
      (node (ref "D17") (pin "1") (pinfunction "C_1") (pintype "unspecified"))
      (node (ref "S17") (pin "2") (pinfunction "2_2") (pintype "input"))
    )
    (net (code "36") (name "Net-(D18-C)") (class "Default")
      (node (ref "D18") (pin "1") (pinfunction "C_1") (pintype "unspecified"))
      (node (ref "S18") (pin "2") (pinfunction "2_2") (pintype "input"))
    )
    (net (code "37") (name "Net-(D19-C)") (class "Default")
      (node (ref "D19") (pin "1") (pinfunction "C_1") (pintype "unspecified"))
      (node (ref "S19") (pin "2") (pinfunction "2_2") (pintype "input"))
    )
    (net (code "38") (name "Net-(D20-C)") (class "Default")
      (node (ref "D20") (pin "1") (pinfunction "C_1") (pintype "unspecified"))
      (node (ref "S20") (pin "2") (pinfunction "2_2") (pintype "input"))
    )
    (net (code "39") (name "Net-(LED21-DIN)") (class "Default")
      (node (ref "LED21") (pin "4") (pinfunction "DIN_4") (pintype "unspecified"))
      (node (ref "LED22") (pin "2") (pinfunction "DOUT_2") (pintype "unspecified"))
    )
    (net (code "40") (name "Net-(LED22-DIN)") (class "Default")
      (node (ref "LED22") (pin "4") (pinfunction "DIN_4") (pintype "unspecified"))
      (node (ref "LED23") (pin "2") (pinfunction "DOUT_2") (pintype "unspecified"))
    )
    (net (code "41") (name "Net-(LED23-DIN)") (class "Default")
      (node (ref "LED23") (pin "4") (pinfunction "DIN_4") (pintype "unspecified"))
      (node (ref "LED24") (pin "2") (pinfunction "DOUT_2") (pintype "unspecified"))
    )
    (net (code "42") (name "Net-(LED24-DIN)") (class "Default")
      (node (ref "LED24") (pin "4") (pinfunction "DIN_4") (pintype "unspecified"))
      (node (ref "LED25") (pin "2") (pinfunction "DOUT_2") (pintype "unspecified"))
    )
    (net (code "43") (name "Net-(LED25-DIN)") (class "Default")
      (node (ref "LED25") (pin "4") (pinfunction "DIN_4") (pintype "unspecified"))
      (node (ref "LED26") (pin "2") (pinfunction "DOUT_2") (pintype "unspecified"))
    )
    (net (code "44") (name "Net-(LED26-DIN)") (class "Default")
      (node (ref "LED26") (pin "4") (pinfunction "DIN_4") (pintype "unspecified"))
      (node (ref "LED27") (pin "2") (pinfunction "DOUT_2") (pintype "unspecified"))
    )
    (net (code "45") (name "Net-(LED27-DIN)") (class "Default")
      (node (ref "LED27") (pin "4") (pinfunction "DIN_4") (pintype "unspecified"))
      (node (ref "LED28") (pin "2") (pinfunction "DOUT_2") (pintype "unspecified"))
    )
    (net (code "46") (name "Net-(LED28-DIN)") (class "Default")
      (node (ref "LED28") (pin "4") (pinfunction "DIN_4") (pintype "unspecified"))
      (node (ref "LED29") (pin "2") (pinfunction "DOUT_2") (pintype "unspecified"))
    )
    (net (code "47") (name "Net-(LED29-DIN)") (class "Default")
      (node (ref "LED29") (pin "4") (pinfunction "DIN_4") (pintype "unspecified"))
      (node (ref "LED30") (pin "2") (pinfunction "DOUT_2") (pintype "unspecified"))
    )
    (net (code "48") (name "Net-(LED30-DIN)") (class "Default")
      (node (ref "LED30") (pin "4") (pinfunction "DIN_4") (pintype "unspecified"))
      (node (ref "LED31") (pin "2") (pinfunction "DOUT_2") (pintype "unspecified"))
    )
    (net (code "49") (name "Net-(LED31-DIN)") (class "Default")
      (node (ref "LED31") (pin "4") (pinfunction "DIN_4") (pintype "unspecified"))
      (node (ref "LED32") (pin "2") (pinfunction "DOUT_2") (pintype "unspecified"))
    )
    (net (code "50") (name "Net-(LED32-DIN)") (class "Default")
      (node (ref "LED32") (pin "4") (pinfunction "DIN_4") (pintype "unspecified"))
      (node (ref "LED33") (pin "2") (pinfunction "DOUT_2") (pintype "unspecified"))
    )
    (net (code "51") (name "Net-(LED33-DIN)") (class "Default")
      (node (ref "LED33") (pin "4") (pinfunction "DIN_4") (pintype "unspecified"))
      (node (ref "LED34") (pin "2") (pinfunction "DOUT_2") (pintype "unspecified"))
    )
    (net (code "52") (name "Net-(LED34-DIN)") (class "Default")
      (node (ref "LED34") (pin "4") (pinfunction "DIN_4") (pintype "unspecified"))
      (node (ref "LED35") (pin "2") (pinfunction "DOUT_2") (pintype "unspecified"))
    )
    (net (code "53") (name "Net-(LED35-DIN)") (class "Default")
      (node (ref "LED35") (pin "4") (pinfunction "DIN_4") (pintype "unspecified"))
      (node (ref "LED36") (pin "2") (pinfunction "DOUT_2") (pintype "unspecified"))
    )
    (net (code "54") (name "Net-(LED36-DIN)") (class "Default")
      (node (ref "LED36") (pin "4") (pinfunction "DIN_4") (pintype "unspecified"))
      (node (ref "LED37") (pin "2") (pinfunction "DOUT_2") (pintype "unspecified"))
    )
    (net (code "55") (name "Net-(LED37-DIN)") (class "Default")
      (node (ref "LED37") (pin "4") (pinfunction "DIN_4") (pintype "unspecified"))
      (node (ref "LED38") (pin "2") (pinfunction "DOUT_2") (pintype "unspecified"))
    )
    (net (code "56") (name "Net-(LED38-DIN)") (class "Default")
      (node (ref "LED38") (pin "4") (pinfunction "DIN_4") (pintype "unspecified"))
      (node (ref "LED39") (pin "2") (pinfunction "DOUT_2") (pintype "unspecified"))
    )
    (net (code "57") (name "Net-(LED39-DIN)") (class "Default")
      (node (ref "LED39") (pin "4") (pinfunction "DIN_4") (pintype "unspecified"))
      (node (ref "LED40") (pin "2") (pinfunction "DOUT_2") (pintype "unspecified"))
    )
    (net (code "58") (name "Net-(P2-Pad1)") (class "Default")
      (node (ref "P2") (pin "1") (pinfunction "1_1") (pintype "input"))
      (node (ref "P3") (pin "1") (pinfunction "1_1") (pintype "input"))
      (node (ref "Volume_Slider") (pin "1") (pinfunction "1_1") (pintype "unspecified"))
    )
    (net (code "59") (name "Net-(U6-Y)") (class "Default")
      (node (ref "R5") (pin "1") (pinfunction "1_1") (pintype "unspecified"))
      (node (ref "U6") (pin "4") (pinfunction "Y_4") (pintype "input"))
    )
    (net (code "60") (name "Net-(USB1-CC1)") (class "Default")
      (node (ref "R1") (pin "2") (pinfunction "2_2") (pintype "unspecified"))
      (node (ref "USB1") (pin "A5") (pinfunction "CC1_A5") (pintype "unspecified"))
    )
    (net (code "61") (name "Net-(USB1-CC2)") (class "Default")
      (node (ref "R2") (pin "2") (pinfunction "2_2") (pintype "unspecified"))
      (node (ref "USB1") (pin "B5") (pinfunction "CC2_B5") (pintype "unspecified"))
    )
    (net (code "62") (name "RESET") (class "Default")
      (node (ref "RESET") (pin "1") (pinfunction "1_1") (pintype "unspecified"))
      (node (ref "RaspberryPiPico2W") (pin "30") (pinfunction "RUN_30") (pintype "unspecified"))
    )
    (net (code "63") (name "ROW1") (class "Default")
      (node (ref "D1") (pin "2") (pinfunction "A_2") (pintype "unspecified"))
      (node (ref "D13") (pin "2") (pinfunction "A_2") (pintype "unspecified"))
      (node (ref "D17") (pin "2") (pinfunction "A_2") (pintype "unspecified"))
      (node (ref "D5") (pin "2") (pinfunction "A_2") (pintype "unspecified"))
      (node (ref "D9") (pin "2") (pinfunction "A_2") (pintype "unspecified"))
      (node (ref "RaspberryPiPico2W") (pin "1") (pinfunction "GP0_SPI0RX_I2C0SDA_UART0TX_1") (pintype "unspecified"))
    )
    (net (code "64") (name "ROW2") (class "Default")
      (node (ref "D10") (pin "2") (pinfunction "A_2") (pintype "unspecified"))
      (node (ref "D14") (pin "2") (pinfunction "A_2") (pintype "unspecified"))
      (node (ref "D18") (pin "2") (pinfunction "A_2") (pintype "unspecified"))
      (node (ref "D2") (pin "2") (pinfunction "A_2") (pintype "unspecified"))
      (node (ref "D6") (pin "2") (pinfunction "A_2") (pintype "unspecified"))
      (node (ref "RaspberryPiPico2W") (pin "2") (pinfunction "GP1_SPI0CSn_I2C0SCL_UART0RX_2") (pintype "unspecified"))
    )
    (net (code "65") (name "ROW3") (class "Default")
      (node (ref "D11") (pin "2") (pinfunction "A_2") (pintype "unspecified"))
      (node (ref "D15") (pin "2") (pinfunction "A_2") (pintype "unspecified"))
      (node (ref "D19") (pin "2") (pinfunction "A_2") (pintype "unspecified"))
      (node (ref "D3") (pin "2") (pinfunction "A_2") (pintype "unspecified"))
      (node (ref "D7") (pin "2") (pinfunction "A_2") (pintype "unspecified"))
      (node (ref "RaspberryPiPico2W") (pin "4") (pinfunction "GP2_SPI0SCK_I2C1SDA_4") (pintype "unspecified"))
    )
    (net (code "66") (name "ROW4") (class "Default")
      (node (ref "D12") (pin "2") (pinfunction "A_2") (pintype "unspecified"))
      (node (ref "D16") (pin "2") (pinfunction "A_2") (pintype "unspecified"))
      (node (ref "D20") (pin "2") (pinfunction "A_2") (pintype "unspecified"))
      (node (ref "D4") (pin "2") (pinfunction "A_2") (pintype "unspecified"))
      (node (ref "D8") (pin "2") (pinfunction "A_2") (pintype "unspecified"))
      (node (ref "RaspberryPiPico2W") (pin "5") (pinfunction "GP3_SPI0TX_I2C1SCL_5") (pintype "unspecified"))
    )
    (net (code "67") (name "SCL") (class "Default")
      (node (ref "RaspberryPiPico2W") (pin "17") (pinfunction "GP13_SPI1CSn_I2C0SCL_UART0RX_17") (pintype "unspecified"))
    )
    (net (code "68") (name "SCL1") (class "Default")
      (node (ref "OLED_Female_P") (pin "2") (pinfunction "2_2") (pintype "input"))
      (node (ref "RaspberryPiPico2W") (pin "27") (pinfunction "GP21_I2C0SCL_27") (pintype "unspecified"))
    )
    (net (code "69") (name "SDA") (class "Default")
      (node (ref "RaspberryPiPico2W") (pin "16") (pinfunction "GP12_SPI1RX_I2C0SDA_UART0TX_16") (pintype "unspecified"))
    )
    (net (code "70") (name "SDA1") (class "Default")
      (node (ref "OLED_Female_P") (pin "1") (pinfunction "1_1") (pintype "input"))
      (node (ref "RaspberryPiPico2W") (pin "26") (pinfunction "GP20_I2C0SDA_26") (pintype "unspecified"))
    )
    (net (code "71") (name "SLIDER") (class "Default")
      (node (ref "RaspberryPiPico2W") (pin "34") (pinfunction "GP28_ADC2_34") (pintype "unspecified"))
      (node (ref "Volume_Slider") (pin "2") (pinfunction "2_2") (pintype "unspecified"))
    )
    (net (code "72") (name "SW1A") (class "Default")
      (node (ref "C42") (pin "2") (pinfunction "2_2") (pintype "input"))
      (node (ref "Encoder") (pin "A") (pinfunction "A_A") (pintype "unspecified"))
      (node (ref "R4") (pin "2") (pinfunction "2_2") (pintype "unspecified"))
      (node (ref "RaspberryPiPico2W") (pin "14") (pinfunction "GP10_SPI1SCK_I2C1SDA_14") (pintype "unspecified"))
    )
    (net (code "73") (name "SW1B") (class "Default")
      (node (ref "C41") (pin "2") (pinfunction "2_2") (pintype "input"))
      (node (ref "Encoder") (pin "B") (pinfunction "B_B") (pintype "unspecified"))
      (node (ref "R3") (pin "1") (pinfunction "1_1") (pintype "unspecified"))
      (node (ref "RaspberryPiPico2W") (pin "15") (pinfunction "GP11_SPI1TX_I2C1SCL_15") (pintype "unspecified"))
    )
    (net (code "74") (name "unconnected-(Encoder-Pad6)") (class "Default")
      (node (ref "Encoder") (pin "6") (pinfunction "6_6") (pintype "unspecified+no_connect"))
    )
    (net (code "75") (name "unconnected-(Encoder-Pad7)") (class "Default")
      (node (ref "Encoder") (pin "7") (pinfunction "7_7") (pintype "unspecified+no_connect"))
    )
    (net (code "76") (name "unconnected-(LED21-DOUT-Pad2)") (class "Default")
      (node (ref "LED21") (pin "2") (pinfunction "DOUT_2") (pintype "unspecified"))
    )
    (net (code "77") (name "unconnected-(RaspberryPiPico2W-3V3_EN-Pad37)") (class "Default")
      (node (ref "RaspberryPiPico2W") (pin "37") (pinfunction "3V3_EN_37") (pintype "unspecified"))
    )
    (net (code "78") (name "unconnected-(RaspberryPiPico2W-ADC_VREF-Pad35)") (class "Default")
      (node (ref "RaspberryPiPico2W") (pin "35") (pinfunction "ADC_VREF_35") (pintype "unspecified"))
    )
    (net (code "79") (name "unconnected-(RaspberryPiPico2W-GP15_SPI1TX_I2C1SCL-Pad20)") (class "Default")
      (node (ref "RaspberryPiPico2W") (pin "20") (pinfunction "GP15_SPI1TX_I2C1SCL_20") (pintype "unspecified"))
    )
    (net (code "80") (name "unconnected-(RaspberryPiPico2W-GP16_SPI0RX_UART0RX-Pad21)") (class "Default")
      (node (ref "RaspberryPiPico2W") (pin "21") (pinfunction "GP16_SPI0RX_UART0RX_21") (pintype "unspecified"))
    )
    (net (code "81") (name "unconnected-(RaspberryPiPico2W-GP17_SPI0CSn_UART0TX-Pad22)") (class "Default")
      (node (ref "RaspberryPiPico2W") (pin "22") (pinfunction "GP17_SPI0CSn_UART0TX_22") (pintype "unspecified"))
    )
    (net (code "82") (name "unconnected-(RaspberryPiPico2W-GP18_SPI0SCK_I2C1SDA-Pad24)") (class "Default")
      (node (ref "RaspberryPiPico2W") (pin "24") (pinfunction "GP18_SPI0SCK_I2C1SDA_24") (pintype "unspecified"))
    )
    (net (code "83") (name "unconnected-(RaspberryPiPico2W-GP19_SPI0TX_I2C1SCL-Pad25)") (class "Default")
      (node (ref "RaspberryPiPico2W") (pin "25") (pinfunction "GP19_SPI0TX_I2C1SCL_25") (pintype "unspecified"))
    )
    (net (code "84") (name "unconnected-(RaspberryPiPico2W-GP22-Pad29)") (class "Default")
      (node (ref "RaspberryPiPico2W") (pin "29") (pinfunction "GP22_29") (pintype "unspecified"))
    )
    (net (code "85") (name "unconnected-(RaspberryPiPico2W-PadTP4)") (class "Default")
      (node (ref "RaspberryPiPico2W") (pin "TP4") (pinfunction "TP4_TP4") (pintype "unspecified"))
    )
    (net (code "86") (name "unconnected-(RaspberryPiPico2W-PadTP5)") (class "Default")
      (node (ref "RaspberryPiPico2W") (pin "TP5") (pinfunction "TP5_TP5") (pintype "unspecified"))
    )
    (net (code "87") (name "unconnected-(RaspberryPiPico2W-VSYS-Pad39)") (class "Default")
      (node (ref "RaspberryPiPico2W") (pin "39") (pinfunction "VSYS_39") (pintype "unspecified"))
    )
    (net (code "88") (name "unconnected-(USB1-SBU1-PadA8)") (class "Default")
      (node (ref "USB1") (pin "A8") (pinfunction "SBU1_A8") (pintype "unspecified+no_connect"))
    )
    (net (code "89") (name "unconnected-(USB1-SBU2-PadB8)") (class "Default")
      (node (ref "USB1") (pin "B8") (pinfunction "SBU2_B8") (pintype "unspecified+no_connect"))
    )
    (net (code "90") (name "unconnected-(Volume_Slider-Pad4)") (class "Default")
      (node (ref "Volume_Slider") (pin "4") (pinfunction "4_4") (pintype "unspecified+no_connect"))
    )
    (net (code "91") (name "unconnected-(Volume_Slider-Pad5)") (class "Default")
      (node (ref "Volume_Slider") (pin "5") (pinfunction "5_5") (pintype "unspecified+no_connect"))
    )
    (net (code "92") (name "unconnected-(Volume_Slider-Pad6)") (class "Default")
      (node (ref "Volume_Slider") (pin "6") (pinfunction "6_6") (pintype "unspecified+no_connect"))
    )
    (net (code "93") (name "unconnected-(Volume_Slider-Pad7)") (class "Default")
      (node (ref "Volume_Slider") (pin "7") (pinfunction "7_7") (pintype "unspecified+no_connect"))
    )
  )
)
